# 03_Power_IO.net
KiCad netlist of a schematic drawn in Altium Designer
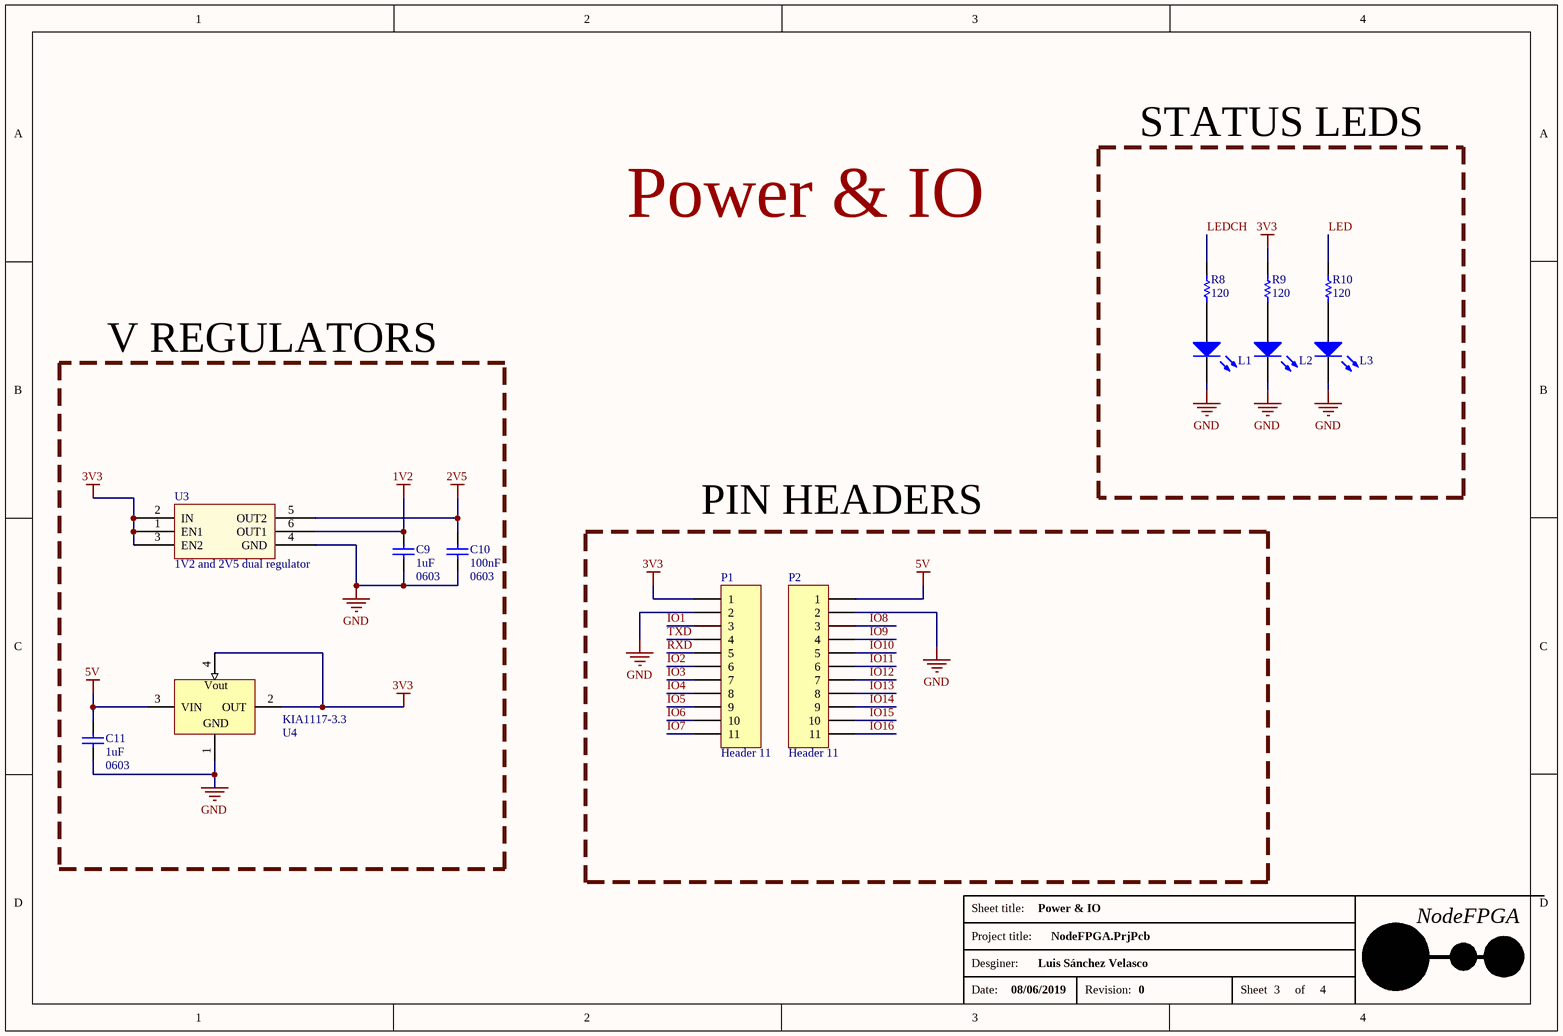
[diagram p0: 03_Power_IO.SchDoc]

(export (version "E")
  (design (tool "Eeschema 10.0.6"))
  (components
    (comp (ref "C9")
      (value "1uF")
      (footprint "0603 CAP")
      (description "Capacitor")
      (fields (field (name "PACKAGE") "0603") (field (name "Comment") "Ceramic capacitor"))
      (libsource (lib "NodeFPGA") (part "Capacitor"))
    )
    (comp (ref "C10")
      (value "100nF")
      (footprint "0603 CAP")
      (description "Capacitor")
      (fields (field (name "PACKAGE") "0603") (field (name "Comment") "Ceramic capacitor"))
      (libsource (lib "NodeFPGA") (part "Capacitor"))
    )
    (comp (ref "C11")
      (value "1uF")
      (footprint "0603 CAP")
      (description "Capacitor")
      (fields (field (name "PACKAGE") "0603") (field (name "Comment") "Ceramic capacitor"))
      (libsource (lib "NodeFPGA") (part "Capacitor"))
    )
    (comp (ref "L1")
      (value "LED_SMD")
      (footprint "0805")
      (description "LED SMD")
      (libsource (lib "NodeFPGA") (part "LED_SMD"))
    )
    (comp (ref "L2")
      (value "LED_SMD")
      (footprint "0805")
      (description "LED SMD")
      (libsource (lib "NodeFPGA") (part "LED_SMD"))
    )
    (comp (ref "L3")
      (value "LED_SMD")
      (footprint "0805")
      (description "LED SMD")
      (libsource (lib "NodeFPGA") (part "LED_SMD"))
    )
    (comp (ref "P1")
      (value "Header 11")
      (footprint "HDR1X11")
      (description "Header, 11-Pin")
      (fields (field (name "PUBLISHER") "Altium Limited"))
      (libsource (lib "NodeFPGA") (part "Header 11_1"))
    )
    (comp (ref "P2")
      (value "Header 11")
      (footprint "HDR1X11")
      (description "Header, 11-Pin")
      (fields (field (name "PUBLISHER") "Altium Limited"))
      (libsource (lib "") (part "Header 11_1_1"))
    )
    (comp (ref "R8")
      (value "120")
      (footprint "Resistencia 0603")
      (description "Resistor")
      (libsource (lib "OpenFPGA") (part "Resistor"))
    )
    (comp (ref "R9")
      (value "120")
      (footprint "Resistencia 0603")
      (description "Resistor")
      (libsource (lib "OpenFPGA") (part "Resistor"))
    )
    (comp (ref "R10")
      (value "120")
      (footprint "Resistencia 0603")
      (description "Resistor")
      (libsource (lib "OpenFPGA") (part "Resistor"))
    )
    (comp (ref "U3")
      (value "1V2 and 2V5 dual regulator")
      (footprint "DSE 6")
      (libsource (lib "NodeFPGA") (part "TLV7111225DSER"))
    )
    (comp (ref "U4")
      (value "KIA1117-3.3")
      (footprint "SOT-223")
      (description "5V to 3.3V 800mA Low-Dropout Linear Regulator")
      (libsource (lib "NodeFPGA") (part "KIA1117-3.3"))
    )
  )
  (nets
    (net (code "1") (name "/IO1") (class "Default")
      (node (ref "P1") (pin "3") (pinfunction "3_3") (pintype "passive"))
    )
    (net (code "2") (name "/IO2") (class "Default")
      (node (ref "P1") (pin "6") (pinfunction "6_6") (pintype "passive"))
    )
    (net (code "3") (name "/IO3") (class "Default")
      (node (ref "P1") (pin "7") (pinfunction "7_7") (pintype "passive"))
    )
    (net (code "4") (name "/IO4") (class "Default")
      (node (ref "P1") (pin "8") (pinfunction "8_8") (pintype "passive"))
    )
    (net (code "5") (name "/IO5") (class "Default")
      (node (ref "P1") (pin "9") (pinfunction "9_9") (pintype "passive"))
    )
    (net (code "6") (name "/IO6") (class "Default")
      (node (ref "P1") (pin "10") (pinfunction "10_10") (pintype "passive"))
    )
    (net (code "7") (name "/IO7") (class "Default")
      (node (ref "P1") (pin "11") (pinfunction "11_11") (pintype "passive"))
    )
    (net (code "8") (name "/IO8") (class "Default")
      (node (ref "P2") (pin "3") (pinfunction "3_3") (pintype "passive"))
    )
    (net (code "9") (name "/IO9") (class "Default")
      (node (ref "P2") (pin "4") (pinfunction "4_4") (pintype "passive"))
    )
    (net (code "10") (name "/IO10") (class "Default")
      (node (ref "P2") (pin "5") (pinfunction "5_5") (pintype "passive"))
    )
    (net (code "11") (name "/IO11") (class "Default")
      (node (ref "P2") (pin "6") (pinfunction "6_6") (pintype "passive"))
    )
    (net (code "12") (name "/IO12") (class "Default")
      (node (ref "P2") (pin "7") (pinfunction "7_7") (pintype "passive"))
    )
    (net (code "13") (name "/IO13") (class "Default")
      (node (ref "P2") (pin "8") (pinfunction "8_8") (pintype "passive"))
    )
    (net (code "14") (name "/IO14") (class "Default")
      (node (ref "P2") (pin "9") (pinfunction "9_9") (pintype "passive"))
    )
    (net (code "15") (name "/IO15") (class "Default")
      (node (ref "P2") (pin "10") (pinfunction "10_10") (pintype "passive"))
    )
    (net (code "16") (name "/IO16") (class "Default")
      (node (ref "P2") (pin "11") (pinfunction "11_11") (pintype "passive"))
    )
    (net (code "17") (name "/LED") (class "Default")
      (node (ref "R10") (pin "2") (pinfunction "2_2") (pintype "passive"))
    )
    (net (code "18") (name "/LEDCH") (class "Default")
      (node (ref "R8") (pin "2") (pinfunction "2_2") (pintype "passive"))
    )
    (net (code "19") (name "/RXD") (class "Default")
      (node (ref "P1") (pin "5") (pinfunction "5_5") (pintype "passive"))
    )
    (net (code "20") (name "/TXD") (class "Default")
      (node (ref "P1") (pin "4") (pinfunction "4_4") (pintype "passive"))
    )
    (net (code "21") (name "1V2") (class "Default")
      (node (ref "C9") (pin "1") (pinfunction "1_1") (pintype "passive"))
      (node (ref "U3") (pin "6") (pinfunction "OUT1_6") (pintype "passive"))
    )
    (net (code "22") (name "2V5") (class "Default")
      (node (ref "C10") (pin "1") (pinfunction "1_1") (pintype "passive"))
      (node (ref "U3") (pin "5") (pinfunction "OUT2_5") (pintype "passive"))
    )
    (net (code "23") (name "3V3") (class "Default")
      (node (ref "P1") (pin "1") (pinfunction "1_1") (pintype "passive"))
      (node (ref "R9") (pin "2") (pinfunction "2_2") (pintype "passive"))
      (node (ref "U3") (pin "1") (pinfunction "EN1_1") (pintype "passive"))
      (node (ref "U3") (pin "2") (pinfunction "IN_2") (pintype "passive"))
      (node (ref "U3") (pin "3") (pinfunction "EN2_3") (pintype "passive"))
      (node (ref "U4") (pin "2") (pinfunction "OUT_2") (pintype "passive"))
      (node (ref "U4") (pin "4") (pinfunction "Vout_4") (pintype "input"))
    )
    (net (code "24") (name "5V") (class "Default")
      (node (ref "C11") (pin "1") (pinfunction "1_1") (pintype "passive"))
      (node (ref "P2") (pin "1") (pinfunction "1_1") (pintype "passive"))
      (node (ref "U4") (pin "3") (pinfunction "VIN_3") (pintype "power_in"))
    )
    (net (code "25") (name "GND") (class "Default")
      (node (ref "C10") (pin "2") (pinfunction "2_2") (pintype "passive"))
      (node (ref "C11") (pin "2") (pinfunction "2_2") (pintype "passive"))
      (node (ref "C9") (pin "2") (pinfunction "2_2") (pintype "passive"))
      (node (ref "L1") (pin "2") (pinfunction "K_2") (pintype "passive"))
      (node (ref "L2") (pin "2") (pinfunction "K_2") (pintype "passive"))
      (node (ref "L3") (pin "2") (pinfunction "K_2") (pintype "passive"))
      (node (ref "P1") (pin "2") (pinfunction "2_2") (pintype "passive"))
      (node (ref "P2") (pin "2") (pinfunction "2_2") (pintype "passive"))
      (node (ref "U3") (pin "4") (pinfunction "GND_4") (pintype "passive"))
      (node (ref "U4") (pin "1") (pinfunction "GND_1") (pintype "power_in"))
    )
    (net (code "26") (name "Net-(L1-A)") (class "Default")
      (node (ref "L1") (pin "1") (pinfunction "A_1") (pintype "passive"))
      (node (ref "R8") (pin "1") (pinfunction "1_1") (pintype "passive"))
    )
    (net (code "27") (name "Net-(L2-A)") (class "Default")
      (node (ref "L2") (pin "1") (pinfunction "A_1") (pintype "passive"))
      (node (ref "R9") (pin "1") (pinfunction "1_1") (pintype "passive"))
    )
    (net (code "28") (name "Net-(L3-A)") (class "Default")
      (node (ref "L3") (pin "1") (pinfunction "A_1") (pintype "passive"))
      (node (ref "R10") (pin "1") (pinfunction "1_1") (pintype "passive"))
    )
  )
)
